# STRWHL-S04-V00-PSU-LEDs.net
KiCad netlist of a schematic drawn in Altium Designer
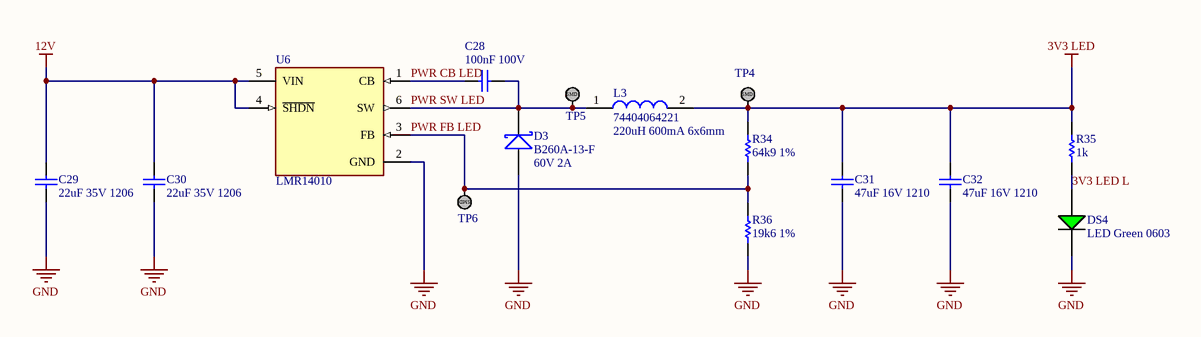
[diagram p0: STRWHL-S04-V00-PSU-LEDs.SchDoc]

(export (version "E")
  (design (tool "Eeschema 10.0.6"))
  (components
    (comp (ref "C28")
      (value "100nF 100V")
      (footprint "Cap_Ceramic_0603")
      (description "Capacitor, Ceramic, SMD, 100nF, 100V, 5%, X7R, 0603")
      (libsource (lib "StandardCapacitors") (part "100nF 100V 5% X7R 0603"))
    )
    (comp (ref "C29")
      (value "22uF 35V 1206")
      (footprint "Cap_Ceramic_1206")
      (description "Capacitor, Ceramic, SMD, 22uF, 35V, 10%, X7R, 1206")
      (libsource (lib "StandardCapacitors") (part "22uF 35V 10% X7R 1206"))
    )
    (comp (ref "C30")
      (value "22uF 35V 1206")
      (footprint "Cap_Ceramic_1206")
      (description "Capacitor, Ceramic, SMD, 22uF, 35V, 10%, X7R, 1206")
      (libsource (lib "StandardCapacitors") (part "22uF 35V 10% X7R 1206"))
    )
    (comp (ref "C31")
      (value "47uF 16V 1210")
      (footprint "Cap_Ceramic_1210")
      (description "Capacitor, Ceramic, SMD, 47uF, 16V, 5%, X7R, 1210")
      (libsource (lib "StandardCapacitors") (part "47uF 16V 10% X7R 1210"))
    )
    (comp (ref "C32")
      (value "47uF 16V 1210")
      (footprint "Cap_Ceramic_1210")
      (description "Capacitor, Ceramic, SMD, 47uF, 16V, 5%, X7R, 1210")
      (libsource (lib "StandardCapacitors") (part "47uF 16V 10% X7R 1210"))
    )
    (comp (ref "D3")
      (value "B260A-13-F")
      (footprint "SMA")
      (description "Diode, Schottky Barrier Rectifier, 60 V, 2 A, B260A-13-F")
      (libsource (lib "QUTMS_DiodeLibrary") (part "B260A-13-F"))
    )
    (comp (ref "DS4")
      (value "LED Green 0603")
      (footprint "LED GREEN 0603")
      (libsource (lib "QUTMS_LEDLibrary") (part "LED Green 0603"))
    )
    (comp (ref "L3")
      (value "74404064221")
      (footprint "Inductor_6x6mm")
      (description "FIXED IND 220UH 660MA 850 MOHM")
      (libsource (lib "QUTMS_InductorLibrary") (part "74404064221"))
    )
    (comp (ref "R34")
      (value "64k9 1%")
      (footprint "Res_ThinFilm_0603")
      (description "Resistor, SMD, 64k9, 0.1W, 5%, 0603")
      (libsource (lib "StandardResistors") (part "64k9 1% 0603"))
    )
    (comp (ref "R35")
      (value "1k")
      (footprint "Res_ThinFilm_0603")
      (description "Resistor, SMD, 1k, 0.1W, 5%, 0603")
      (libsource (lib "StandardResistors") (part "1k 5% 0603"))
    )
    (comp (ref "R36")
      (value "19k6 1%")
      (footprint "Res_ThinFilm_0603")
      (description "Resistor, SMD, 19k6, 0.1W, 5%, 0603")
      (libsource (lib "StandardResistors") (part "19k6 1% 0603"))
    )
    (comp (ref "TP4")
      (value "TestPoint_SMD")
      (footprint "TestPointSMD")
      (libsource (lib "StandardTest") (part "TestPoint_SMD"))
    )
    (comp (ref "TP5")
      (value "TestPoint_SMD")
      (footprint "TestPointSMD")
      (libsource (lib "StandardTest") (part "TestPoint_SMD"))
    )
    (comp (ref "TP6")
      (value "TestPoint_SMD")
      (footprint "TestPointSMD")
      (libsource (lib "StandardTest") (part "TestPoint_SMD"))
    )
    (comp (ref "U6")
      (value "LMR14010")
      (footprint "LMR14010")
      (libsource (lib "QUTMS_PowerSupplyLibrary") (part "LMR14010"))
    )
  )
  (nets
    (net (code "1") (name "/3V3 LED L") (class "Default")
      (node (ref "DS4") (pin "1") (pinfunction "A_1") (pintype "passive"))
      (node (ref "R35") (pin "1") (pinfunction "1_1") (pintype "passive"))
    )
    (net (code "2") (name "/PWR CB LED") (class "Default")
      (node (ref "C28") (pin "1") (pinfunction "1_1") (pintype "passive"))
      (node (ref "U6") (pin "1") (pinfunction "CB_1") (pintype "input"))
    )
    (net (code "3") (name "/PWR FB LED") (class "Default")
      (node (ref "R34") (pin "1") (pinfunction "1_1") (pintype "passive"))
      (node (ref "R36") (pin "2") (pinfunction "2_2") (pintype "passive"))
      (node (ref "TP6") (pin "1") (pinfunction "1_1") (pintype "passive"))
      (node (ref "U6") (pin "3") (pinfunction "FB_3") (pintype "input"))
    )
    (net (code "4") (name "/PWR SW LED") (class "Default")
      (node (ref "C28") (pin "2") (pinfunction "2_2") (pintype "passive"))
      (node (ref "D3") (pin "K") (pinfunction "K_K") (pintype "passive"))
      (node (ref "L3") (pin "1") (pinfunction "1_1") (pintype "passive"))
      (node (ref "TP5") (pin "1") (pinfunction "1_1") (pintype "passive"))
      (node (ref "U6") (pin "6") (pinfunction "SW_6") (pintype "output"))
    )
    (net (code "5") (name "3V3 LED") (class "Default")
      (node (ref "C31") (pin "2") (pinfunction "2_2") (pintype "passive"))
      (node (ref "C32") (pin "2") (pinfunction "2_2") (pintype "passive"))
      (node (ref "L3") (pin "2") (pinfunction "2_2") (pintype "passive"))
      (node (ref "R34") (pin "2") (pinfunction "2_2") (pintype "passive"))
      (node (ref "R35") (pin "2") (pinfunction "2_2") (pintype "passive"))
      (node (ref "TP4") (pin "1") (pinfunction "1_1") (pintype "passive"))
    )
    (net (code "6") (name "12V") (class "Default")
      (node (ref "C29") (pin "2") (pinfunction "2_2") (pintype "passive"))
      (node (ref "C30") (pin "2") (pinfunction "2_2") (pintype "passive"))
      (node (ref "U6") (pin "4") (pinfunction "~{SHDN}_4") (pintype "input"))
      (node (ref "U6") (pin "5") (pinfunction "VIN_5") (pintype "power_in"))
    )
    (net (code "7") (name "GND") (class "Default")
      (node (ref "C29") (pin "1") (pinfunction "1_1") (pintype "passive"))
      (node (ref "C30") (pin "1") (pinfunction "1_1") (pintype "passive"))
      (node (ref "C31") (pin "1") (pinfunction "1_1") (pintype "passive"))
      (node (ref "C32") (pin "1") (pinfunction "1_1") (pintype "passive"))
      (node (ref "D3") (pin "A") (pinfunction "A_A") (pintype "passive"))
      (node (ref "DS4") (pin "2") (pinfunction "C_2") (pintype "passive"))
      (node (ref "R36") (pin "1") (pinfunction "1_1") (pintype "passive"))
      (node (ref "U6") (pin "2") (pinfunction "GND_2") (pintype "power_in"))
    )
  )
)
